# IO.net
KiCad netlist of a schematic drawn in Altium Designer
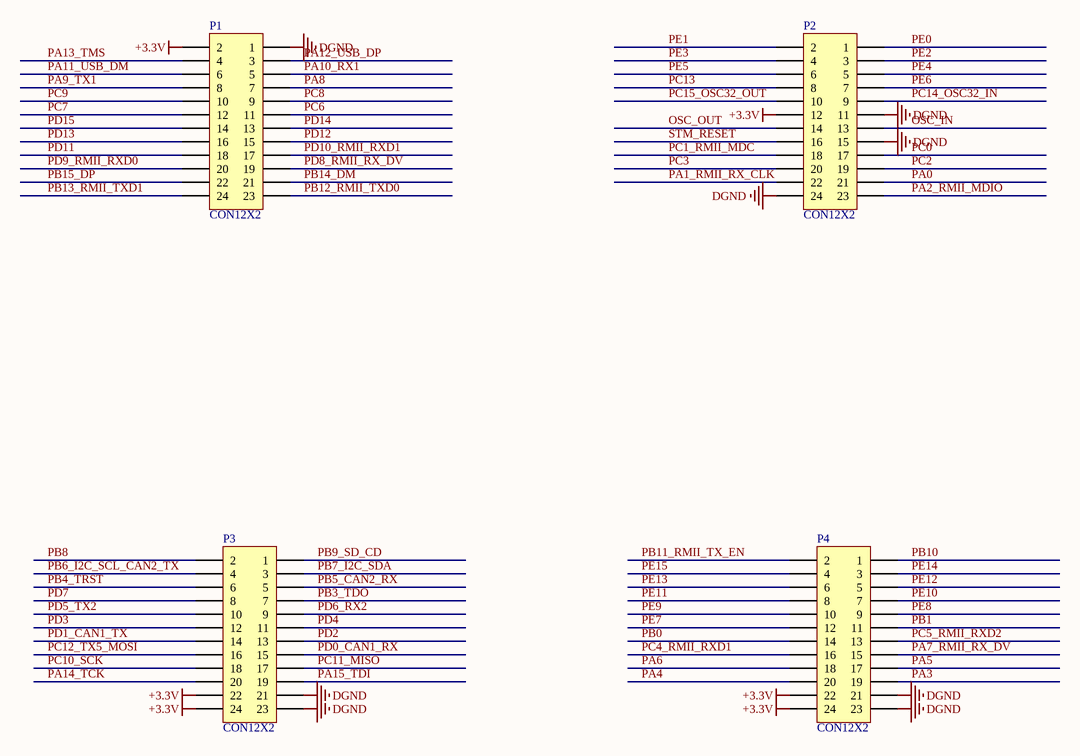
[diagram p0: IO.SchDoc]

(export (version "E")
  (design (tool "Eeschema 10.0.6"))
  (components
    (comp (ref "P1")
      (value "CON12X2")
      (footprint "HDR2X12-2.54MM")
      (description "Header, 12-Pin, Dual row")
      (fields (field (name "PUBLISHER") "Altium Limited"))
      (libsource (lib "Connector_Veiko") (part "CON12X2"))
    )
    (comp (ref "P2")
      (value "CON12X2")
      (footprint "HDR2X12-2.54MM")
      (description "Header, 12-Pin, Dual row")
      (fields (field (name "PUBLISHER") "Altium Limited"))
      (libsource (lib "Connector_Veiko") (part "CON12X2"))
    )
    (comp (ref "P3")
      (value "CON12X2")
      (footprint "HDR2X12-2.54MM")
      (description "Header, 12-Pin, Dual row")
      (fields (field (name "PUBLISHER") "Altium Limited"))
      (libsource (lib "Connector_Veiko") (part "CON12X2"))
    )
    (comp (ref "P4")
      (value "CON12X2")
      (footprint "HDR2X12-2.54MM")
      (description "Header, 12-Pin, Dual row")
      (fields (field (name "PUBLISHER") "Altium Limited"))
      (libsource (lib "Connector_Veiko") (part "CON12X2"))
    )
  )
  (nets
    (net (code "1") (name "+3.3V") (class "Default")
      (node (ref "P1") (pin "2") (pinfunction "2_2") (pintype "passive"))
      (node (ref "P2") (pin "12") (pinfunction "12_12") (pintype "passive"))
      (node (ref "P3") (pin "22") (pinfunction "22_22") (pintype "passive"))
      (node (ref "P3") (pin "24") (pinfunction "24_24") (pintype "passive"))
      (node (ref "P4") (pin "22") (pinfunction "22_22") (pintype "passive"))
      (node (ref "P4") (pin "24") (pinfunction "24_24") (pintype "passive"))
    )
    (net (code "2") (name "/OSC_IN") (class "Default")
      (node (ref "P2") (pin "13") (pinfunction "13_13") (pintype "passive"))
    )
    (net (code "3") (name "/OSC_OUT") (class "Default")
      (node (ref "P2") (pin "14") (pinfunction "14_14") (pintype "passive"))
    )
    (net (code "4") (name "/PA0") (class "Default")
      (node (ref "P2") (pin "21") (pinfunction "21_21") (pintype "passive"))
    )
    (net (code "5") (name "/PA1_RMII_RX_CLK") (class "Default")
      (node (ref "P2") (pin "22") (pinfunction "22_22") (pintype "passive"))
    )
    (net (code "6") (name "/PA2_RMII_MDIO") (class "Default")
      (node (ref "P2") (pin "23") (pinfunction "23_23") (pintype "passive"))
    )
    (net (code "7") (name "/PA3") (class "Default")
      (node (ref "P4") (pin "19") (pinfunction "19_19") (pintype "passive"))
    )
    (net (code "8") (name "/PA4") (class "Default")
      (node (ref "P4") (pin "20") (pinfunction "20_20") (pintype "passive"))
    )
    (net (code "9") (name "/PA5") (class "Default")
      (node (ref "P4") (pin "17") (pinfunction "17_17") (pintype "passive"))
    )
    (net (code "10") (name "/PA6") (class "Default")
      (node (ref "P4") (pin "18") (pinfunction "18_18") (pintype "passive"))
    )
    (net (code "11") (name "/PA7_RMII_RX_DV") (class "Default")
      (node (ref "P4") (pin "15") (pinfunction "15_15") (pintype "passive"))
    )
    (net (code "12") (name "/PA8") (class "Default")
      (node (ref "P1") (pin "7") (pinfunction "7_7") (pintype "passive"))
    )
    (net (code "13") (name "/PA9_TX1") (class "Default")
      (node (ref "P1") (pin "8") (pinfunction "8_8") (pintype "passive"))
    )
    (net (code "14") (name "/PA10_RX1") (class "Default")
      (node (ref "P1") (pin "5") (pinfunction "5_5") (pintype "passive"))
    )
    (net (code "15") (name "/PA11_USB_DM") (class "Default")
      (node (ref "P1") (pin "6") (pinfunction "6_6") (pintype "passive"))
    )
    (net (code "16") (name "/PA12_USB_DP") (class "Default")
      (node (ref "P1") (pin "3") (pinfunction "3_3") (pintype "passive"))
    )
    (net (code "17") (name "/PA13_TMS") (class "Default")
      (node (ref "P1") (pin "4") (pinfunction "4_4") (pintype "passive"))
    )
    (net (code "18") (name "/PA14_TCK") (class "Default")
      (node (ref "P3") (pin "20") (pinfunction "20_20") (pintype "passive"))
    )
    (net (code "19") (name "/PA15_TDI") (class "Default")
      (node (ref "P3") (pin "19") (pinfunction "19_19") (pintype "passive"))
    )
    (net (code "20") (name "/PB0") (class "Default")
      (node (ref "P4") (pin "14") (pinfunction "14_14") (pintype "passive"))
    )
    (net (code "21") (name "/PB1") (class "Default")
      (node (ref "P4") (pin "11") (pinfunction "11_11") (pintype "passive"))
    )
    (net (code "22") (name "/PB3_TDO") (class "Default")
      (node (ref "P3") (pin "7") (pinfunction "7_7") (pintype "passive"))
    )
    (net (code "23") (name "/PB4_TRST") (class "Default")
      (node (ref "P3") (pin "6") (pinfunction "6_6") (pintype "passive"))
    )
    (net (code "24") (name "/PB5_CAN2_RX") (class "Default")
      (node (ref "P3") (pin "5") (pinfunction "5_5") (pintype "passive"))
    )
    (net (code "25") (name "/PB6_I2C_SCL_CAN2_TX") (class "Default")
      (node (ref "P3") (pin "4") (pinfunction "4_4") (pintype "passive"))
    )
    (net (code "26") (name "/PB7_I2C_SDA") (class "Default")
      (node (ref "P3") (pin "3") (pinfunction "3_3") (pintype "passive"))
    )
    (net (code "27") (name "/PB8") (class "Default")
      (node (ref "P3") (pin "2") (pinfunction "2_2") (pintype "passive"))
    )
    (net (code "28") (name "/PB9_SD_CD") (class "Default")
      (node (ref "P3") (pin "1") (pinfunction "1_1") (pintype "passive"))
    )
    (net (code "29") (name "/PB10") (class "Default")
      (node (ref "P4") (pin "1") (pinfunction "1_1") (pintype "passive"))
    )
    (net (code "30") (name "/PB11_RMII_TX_EN") (class "Default")
      (node (ref "P4") (pin "2") (pinfunction "2_2") (pintype "passive"))
    )
    (net (code "31") (name "/PB12_RMII_TXD0") (class "Default")
      (node (ref "P1") (pin "23") (pinfunction "23_23") (pintype "passive"))
    )
    (net (code "32") (name "/PB13_RMII_TXD1") (class "Default")
      (node (ref "P1") (pin "24") (pinfunction "24_24") (pintype "passive"))
    )
    (net (code "33") (name "/PB14_DM") (class "Default")
      (node (ref "P1") (pin "21") (pinfunction "21_21") (pintype "passive"))
    )
    (net (code "34") (name "/PB15_DP") (class "Default")
      (node (ref "P1") (pin "22") (pinfunction "22_22") (pintype "passive"))
    )
    (net (code "35") (name "/PC0") (class "Default")
      (node (ref "P2") (pin "17") (pinfunction "17_17") (pintype "passive"))
    )
    (net (code "36") (name "/PC1_RMII_MDC") (class "Default")
      (node (ref "P2") (pin "18") (pinfunction "18_18") (pintype "passive"))
    )
    (net (code "37") (name "/PC2") (class "Default")
      (node (ref "P2") (pin "19") (pinfunction "19_19") (pintype "passive"))
    )
    (net (code "38") (name "/PC3") (class "Default")
      (node (ref "P2") (pin "20") (pinfunction "20_20") (pintype "passive"))
    )
    (net (code "39") (name "/PC4_RMII_RXD1") (class "Default")
      (node (ref "P4") (pin "16") (pinfunction "16_16") (pintype "passive"))
    )
    (net (code "40") (name "/PC5_RMII_RXD2") (class "Default")
      (node (ref "P4") (pin "13") (pinfunction "13_13") (pintype "passive"))
    )
    (net (code "41") (name "/PC6") (class "Default")
      (node (ref "P1") (pin "11") (pinfunction "11_11") (pintype "passive"))
    )
    (net (code "42") (name "/PC7") (class "Default")
      (node (ref "P1") (pin "12") (pinfunction "12_12") (pintype "passive"))
    )
    (net (code "43") (name "/PC8") (class "Default")
      (node (ref "P1") (pin "9") (pinfunction "9_9") (pintype "passive"))
    )
    (net (code "44") (name "/PC9") (class "Default")
      (node (ref "P1") (pin "10") (pinfunction "10_10") (pintype "passive"))
    )
    (net (code "45") (name "/PC10_SCK") (class "Default")
      (node (ref "P3") (pin "18") (pinfunction "18_18") (pintype "passive"))
    )
    (net (code "46") (name "/PC11_MISO") (class "Default")
      (node (ref "P3") (pin "17") (pinfunction "17_17") (pintype "passive"))
    )
    (net (code "47") (name "/PC12_TX5_MOSI") (class "Default")
      (node (ref "P3") (pin "16") (pinfunction "16_16") (pintype "passive"))
    )
    (net (code "48") (name "/PC13") (class "Default")
      (node (ref "P2") (pin "8") (pinfunction "8_8") (pintype "passive"))
    )
    (net (code "49") (name "/PC14_OSC32_IN") (class "Default")
      (node (ref "P2") (pin "9") (pinfunction "9_9") (pintype "passive"))
    )
    (net (code "50") (name "/PC15_OSC32_OUT") (class "Default")
      (node (ref "P2") (pin "10") (pinfunction "10_10") (pintype "passive"))
    )
    (net (code "51") (name "/PD0_CAN1_RX") (class "Default")
      (node (ref "P3") (pin "15") (pinfunction "15_15") (pintype "passive"))
    )
    (net (code "52") (name "/PD1_CAN1_TX") (class "Default")
      (node (ref "P3") (pin "14") (pinfunction "14_14") (pintype "passive"))
    )
    (net (code "53") (name "/PD2") (class "Default")
      (node (ref "P3") (pin "13") (pinfunction "13_13") (pintype "passive"))
    )
    (net (code "54") (name "/PD3") (class "Default")
      (node (ref "P3") (pin "12") (pinfunction "12_12") (pintype "passive"))
    )
    (net (code "55") (name "/PD4") (class "Default")
      (node (ref "P3") (pin "11") (pinfunction "11_11") (pintype "passive"))
    )
    (net (code "56") (name "/PD5_TX2") (class "Default")
      (node (ref "P3") (pin "10") (pinfunction "10_10") (pintype "passive"))
    )
    (net (code "57") (name "/PD6_RX2") (class "Default")
      (node (ref "P3") (pin "9") (pinfunction "9_9") (pintype "passive"))
    )
    (net (code "58") (name "/PD7") (class "Default")
      (node (ref "P3") (pin "8") (pinfunction "8_8") (pintype "passive"))
    )
    (net (code "59") (name "/PD8_RMII_RX_DV") (class "Default")
      (node (ref "P1") (pin "19") (pinfunction "19_19") (pintype "passive"))
    )
    (net (code "60") (name "/PD9_RMII_RXD0") (class "Default")
      (node (ref "P1") (pin "20") (pinfunction "20_20") (pintype "passive"))
    )
    (net (code "61") (name "/PD10_RMII_RXD1") (class "Default")
      (node (ref "P1") (pin "17") (pinfunction "17_17") (pintype "passive"))
    )
    (net (code "62") (name "/PD11") (class "Default")
      (node (ref "P1") (pin "18") (pinfunction "18_18") (pintype "passive"))
    )
    (net (code "63") (name "/PD12") (class "Default")
      (node (ref "P1") (pin "15") (pinfunction "15_15") (pintype "passive"))
    )
    (net (code "64") (name "/PD13") (class "Default")
      (node (ref "P1") (pin "16") (pinfunction "16_16") (pintype "passive"))
    )
    (net (code "65") (name "/PD14") (class "Default")
      (node (ref "P1") (pin "13") (pinfunction "13_13") (pintype "passive"))
    )
    (net (code "66") (name "/PD15") (class "Default")
      (node (ref "P1") (pin "14") (pinfunction "14_14") (pintype "passive"))
    )
    (net (code "67") (name "/PE0") (class "Default")
      (node (ref "P2") (pin "1") (pinfunction "1_1") (pintype "passive"))
    )
    (net (code "68") (name "/PE1") (class "Default")
      (node (ref "P2") (pin "2") (pinfunction "2_2") (pintype "passive"))
    )
    (net (code "69") (name "/PE2") (class "Default")
      (node (ref "P2") (pin "3") (pinfunction "3_3") (pintype "passive"))
    )
    (net (code "70") (name "/PE3") (class "Default")
      (node (ref "P2") (pin "4") (pinfunction "4_4") (pintype "passive"))
    )
    (net (code "71") (name "/PE4") (class "Default")
      (node (ref "P2") (pin "5") (pinfunction "5_5") (pintype "passive"))
    )
    (net (code "72") (name "/PE5") (class "Default")
      (node (ref "P2") (pin "6") (pinfunction "6_6") (pintype "passive"))
    )
    (net (code "73") (name "/PE6") (class "Default")
      (node (ref "P2") (pin "7") (pinfunction "7_7") (pintype "passive"))
    )
    (net (code "74") (name "/PE7") (class "Default")
      (node (ref "P4") (pin "12") (pinfunction "12_12") (pintype "passive"))
    )
    (net (code "75") (name "/PE8") (class "Default")
      (node (ref "P4") (pin "9") (pinfunction "9_9") (pintype "passive"))
    )
    (net (code "76") (name "/PE9") (class "Default")
      (node (ref "P4") (pin "10") (pinfunction "10_10") (pintype "passive"))
    )
    (net (code "77") (name "/PE10") (class "Default")
      (node (ref "P4") (pin "7") (pinfunction "7_7") (pintype "passive"))
    )
    (net (code "78") (name "/PE11") (class "Default")
      (node (ref "P4") (pin "8") (pinfunction "8_8") (pintype "passive"))
    )
    (net (code "79") (name "/PE12") (class "Default")
      (node (ref "P4") (pin "5") (pinfunction "5_5") (pintype "passive"))
    )
    (net (code "80") (name "/PE13") (class "Default")
      (node (ref "P4") (pin "6") (pinfunction "6_6") (pintype "passive"))
    )
    (net (code "81") (name "/PE14") (class "Default")
      (node (ref "P4") (pin "3") (pinfunction "3_3") (pintype "passive"))
    )
    (net (code "82") (name "/PE15") (class "Default")
      (node (ref "P4") (pin "4") (pinfunction "4_4") (pintype "passive"))
    )
    (net (code "83") (name "/STM_RESET") (class "Default")
      (node (ref "P2") (pin "16") (pinfunction "16_16") (pintype "passive"))
    )
    (net (code "84") (name "DGND") (class "Default")
      (node (ref "P1") (pin "1") (pinfunction "1_1") (pintype "passive"))
      (node (ref "P2") (pin "11") (pinfunction "11_11") (pintype "passive"))
      (node (ref "P2") (pin "15") (pinfunction "15_15") (pintype "passive"))
      (node (ref "P2") (pin "24") (pinfunction "24_24") (pintype "passive"))
      (node (ref "P3") (pin "21") (pinfunction "21_21") (pintype "passive"))
      (node (ref "P3") (pin "23") (pinfunction "23_23") (pintype "passive"))
      (node (ref "P4") (pin "21") (pinfunction "21_21") (pintype "passive"))
      (node (ref "P4") (pin "23") (pinfunction "23_23") (pintype "passive"))
    )
  )
)
